# ME433.net
KiCad netlist of a schematic drawn in EAGLE
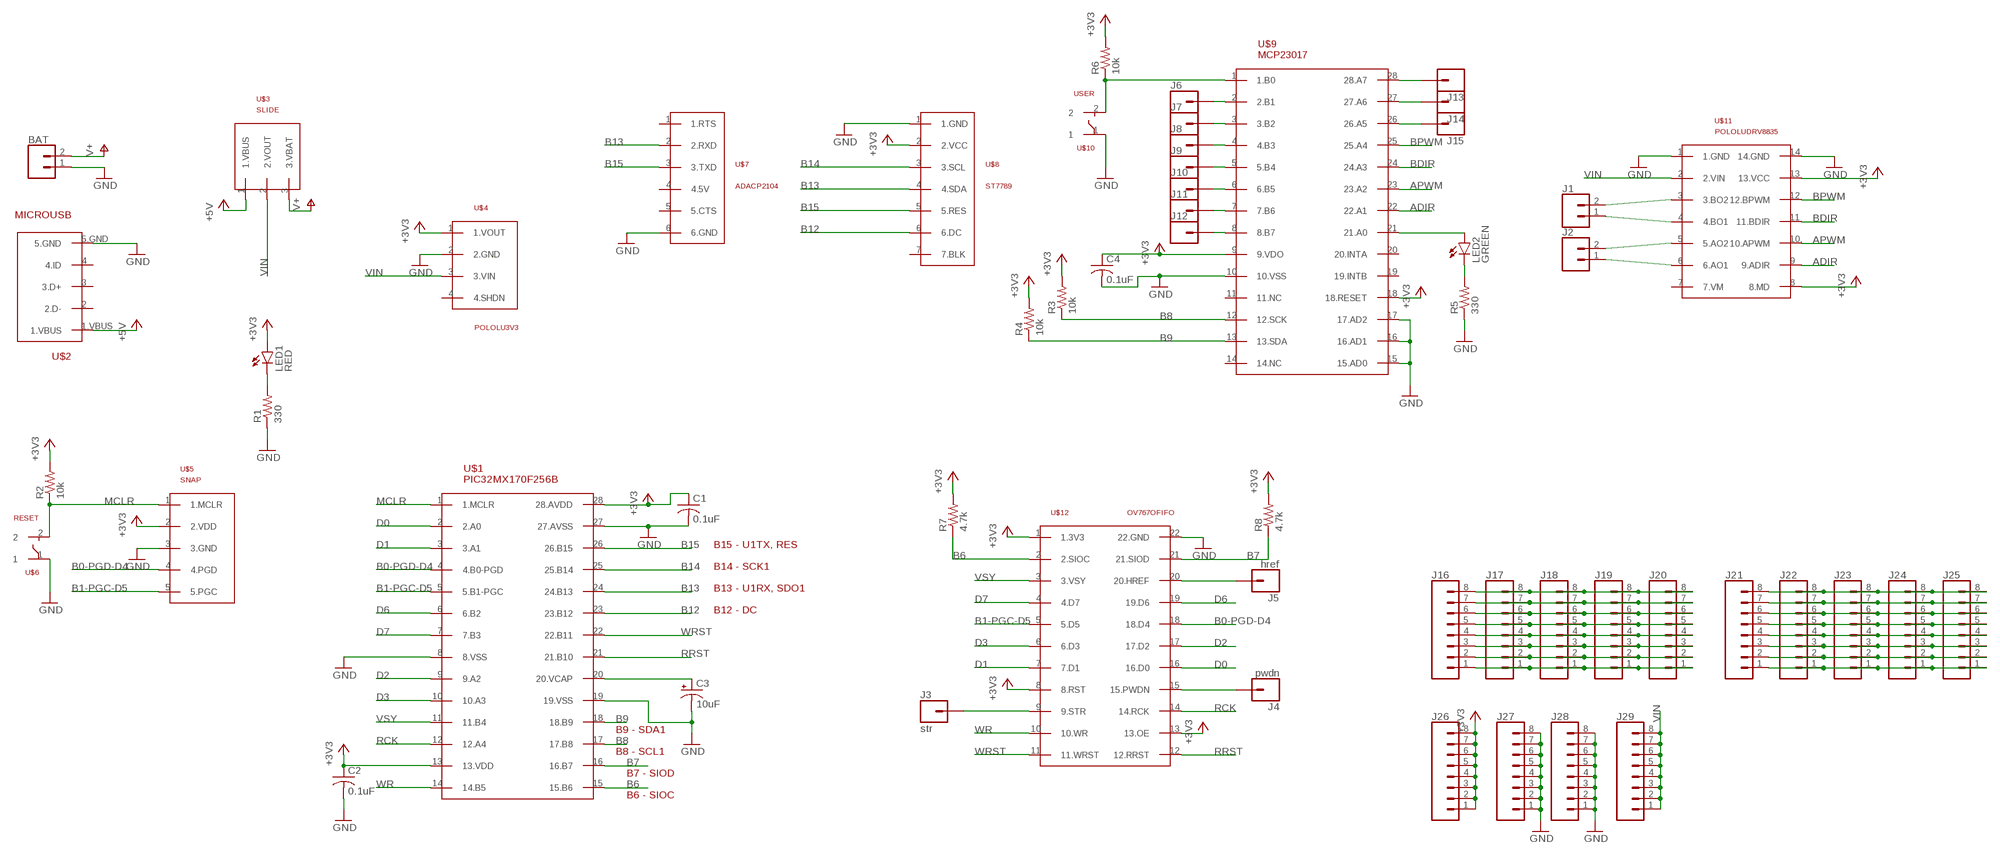
[diagram p0: schematic, sheet 1]

(export (version "E")
  (design (tool "Eeschema 10.0.6"))
  (components
    (comp (ref "BAT")
      (value "CONN_02")
      (footprint "eagle-import:1X02")
      (libsource (lib "eagle-import") (part "CONN_02"))
    )
    (comp (ref "C1")
      (value "0.1uF")
      (footprint "eagle-import:C025-030X050")
      (libsource (lib "eagle-import") (part "C-US025-030X050"))
    )
    (comp (ref "C2")
      (value "0.1uF")
      (footprint "eagle-import:C025-030X050")
      (libsource (lib "eagle-import") (part "C-US025-030X050"))
    )
    (comp (ref "C3")
      (value "10uF")
      (footprint "eagle-import:B45181B")
      (libsource (lib "eagle-import") (part "CPOL-USB45181B"))
    )
    (comp (ref "C4")
      (value "0.1uF")
      (footprint "eagle-import:C025-030X050")
      (libsource (lib "eagle-import") (part "C-US025-030X050"))
    )
    (comp (ref "J1")
      (value "CONN_02")
      (footprint "eagle-import:1X02")
      (libsource (lib "eagle-import") (part "CONN_02"))
    )
    (comp (ref "J2")
      (value "CONN_02")
      (footprint "eagle-import:1X02")
      (libsource (lib "eagle-import") (part "CONN_02"))
    )
    (comp (ref "J3")
      (value "str")
      (footprint "eagle-import:1X01")
      (libsource (lib "eagle-import") (part "CONN_01"))
    )
    (comp (ref "J4")
      (value "pwdn")
      (footprint "eagle-import:1X01")
      (libsource (lib "eagle-import") (part "CONN_01"))
    )
    (comp (ref "J5")
      (value "href")
      (footprint "eagle-import:1X01")
      (libsource (lib "eagle-import") (part "CONN_01"))
    )
    (comp (ref "J6")
      (value "CONN_01")
      (footprint "eagle-import:1X01")
      (libsource (lib "eagle-import") (part "CONN_01"))
    )
    (comp (ref "J7")
      (value "CONN_01")
      (footprint "eagle-import:1X01")
      (libsource (lib "eagle-import") (part "CONN_01"))
    )
    (comp (ref "J8")
      (value "CONN_01")
      (footprint "eagle-import:1X01")
      (libsource (lib "eagle-import") (part "CONN_01"))
    )
    (comp (ref "J9")
      (value "CONN_01")
      (footprint "eagle-import:1X01")
      (libsource (lib "eagle-import") (part "CONN_01"))
    )
    (comp (ref "J10")
      (value "CONN_01")
      (footprint "eagle-import:1X01")
      (libsource (lib "eagle-import") (part "CONN_01"))
    )
    (comp (ref "J11")
      (value "CONN_01")
      (footprint "eagle-import:1X01")
      (libsource (lib "eagle-import") (part "CONN_01"))
    )
    (comp (ref "J12")
      (value "CONN_01")
      (footprint "eagle-import:1X01")
      (libsource (lib "eagle-import") (part "CONN_01"))
    )
    (comp (ref "J13")
      (value "CONN_01")
      (footprint "eagle-import:1X01")
      (libsource (lib "eagle-import") (part "CONN_01"))
    )
    (comp (ref "J14")
      (value "CONN_01")
      (footprint "eagle-import:1X01")
      (libsource (lib "eagle-import") (part "CONN_01"))
    )
    (comp (ref "J15")
      (value "CONN_01")
      (footprint "eagle-import:1X01")
      (libsource (lib "eagle-import") (part "CONN_01"))
    )
    (comp (ref "J16")
      (value "CONN_08\"")
      (footprint "eagle-import:1X08")
      (libsource (lib "eagle-import") (part "CONN_08{dblquote}"))
    )
    (comp (ref "J17")
      (value "CONN_08\"")
      (footprint "eagle-import:1X08")
      (libsource (lib "eagle-import") (part "CONN_08{dblquote}"))
    )
    (comp (ref "J18")
      (value "CONN_08\"")
      (footprint "eagle-import:1X08")
      (libsource (lib "eagle-import") (part "CONN_08{dblquote}"))
    )
    (comp (ref "J19")
      (value "CONN_08\"")
      (footprint "eagle-import:1X08")
      (libsource (lib "eagle-import") (part "CONN_08{dblquote}"))
    )
    (comp (ref "J20")
      (value "CONN_08\"")
      (footprint "eagle-import:1X08")
      (libsource (lib "eagle-import") (part "CONN_08{dblquote}"))
    )
    (comp (ref "J21")
      (value "CONN_08\"")
      (footprint "eagle-import:1X08")
      (libsource (lib "eagle-import") (part "CONN_08{dblquote}"))
    )
    (comp (ref "J22")
      (value "CONN_08\"")
      (footprint "eagle-import:1X08")
      (libsource (lib "eagle-import") (part "CONN_08{dblquote}"))
    )
    (comp (ref "J23")
      (value "CONN_08\"")
      (footprint "eagle-import:1X08")
      (libsource (lib "eagle-import") (part "CONN_08{dblquote}"))
    )
    (comp (ref "J24")
      (value "CONN_08\"")
      (footprint "eagle-import:1X08")
      (libsource (lib "eagle-import") (part "CONN_08{dblquote}"))
    )
    (comp (ref "J25")
      (value "CONN_08\"")
      (footprint "eagle-import:1X08")
      (libsource (lib "eagle-import") (part "CONN_08{dblquote}"))
    )
    (comp (ref "J26")
      (value "CONN_08\"")
      (footprint "eagle-import:1X08")
      (libsource (lib "eagle-import") (part "CONN_08{dblquote}"))
    )
    (comp (ref "J27")
      (value "CONN_08\"")
      (footprint "eagle-import:1X08")
      (libsource (lib "eagle-import") (part "CONN_08{dblquote}"))
    )
    (comp (ref "J28")
      (value "CONN_08\"")
      (footprint "eagle-import:1X08")
      (libsource (lib "eagle-import") (part "CONN_08{dblquote}"))
    )
    (comp (ref "J29")
      (value "CONN_08\"")
      (footprint "eagle-import:1X08")
      (libsource (lib "eagle-import") (part "CONN_08{dblquote}"))
    )
    (comp (ref "LED1")
      (value "RED")
      (footprint "eagle-import:LED3MM")
      (libsource (lib "eagle-import") (part "LED3MM"))
    )
    (comp (ref "LED2")
      (value "GREEN")
      (footprint "eagle-import:LED3MM")
      (libsource (lib "eagle-import") (part "LED3MM"))
    )
    (comp (ref "R1")
      (value "330")
      (footprint "eagle-import:0207_10")
      (libsource (lib "eagle-import") (part "R-US_0207/10"))
    )
    (comp (ref "R2")
      (value "10k")
      (footprint "eagle-import:0207_10")
      (libsource (lib "eagle-import") (part "R-US_0207/10"))
    )
    (comp (ref "R3")
      (value "10k")
      (footprint "eagle-import:0207_10")
      (libsource (lib "eagle-import") (part "R-US_0207/10"))
    )
    (comp (ref "R4")
      (value "10k")
      (footprint "eagle-import:0207_10")
      (libsource (lib "eagle-import") (part "R-US_0207/10"))
    )
    (comp (ref "R5")
      (value "330")
      (footprint "eagle-import:0207_10")
      (libsource (lib "eagle-import") (part "R-US_0207/10"))
    )
    (comp (ref "R6")
      (value "10k")
      (footprint "eagle-import:0207_10")
      (libsource (lib "eagle-import") (part "R-US_0207/10"))
    )
    (comp (ref "R7")
      (value "4.7k")
      (footprint "eagle-import:0207_10")
      (libsource (lib "eagle-import") (part "R-US_0207/10"))
    )
    (comp (ref "R8")
      (value "4.7k")
      (footprint "eagle-import:0207_10")
      (libsource (lib "eagle-import") (part "R-US_0207/10"))
    )
    (comp (ref "U$1")
      (value "PIC32MX170F256B")
      (footprint "eagle-import:DIL28-3")
      (libsource (lib "eagle-import") (part "PIC32MX170F256B"))
    )
    (comp (ref "U$2")
      (value "MICROUSB")
      (footprint "eagle-import:MICROUSB")
      (libsource (lib "eagle-import") (part "MICROUSB"))
    )
    (comp (ref "U$3")
      (value "SLIDE")
      (footprint "eagle-import:SLIDE")
      (libsource (lib "eagle-import") (part "SLIDE"))
    )
    (comp (ref "U$4")
      (value "POLOLU3V3")
      (footprint "eagle-import:POLOLU3V3")
      (libsource (lib "eagle-import") (part "POLOLU3V3"))
    )
    (comp (ref "U$5")
      (value "SNAP")
      (footprint "eagle-import:SNAP")
      (libsource (lib "eagle-import") (part "SNAP"))
    )
    (comp (ref "U$6")
      (value "RESET")
      (footprint "eagle-import:PUSH")
      (libsource (lib "eagle-import") (part "PUSH"))
    )
    (comp (ref "U$7")
      (value "ADACP2104")
      (footprint "eagle-import:ADACP2104")
      (libsource (lib "eagle-import") (part "ADACP2104"))
    )
    (comp (ref "U$8")
      (value "ST7789")
      (footprint "eagle-import:ST7789")
      (libsource (lib "eagle-import") (part "ST7789"))
    )
    (comp (ref "U$9")
      (value "MCP23017")
      (footprint "eagle-import:MCP23017")
      (libsource (lib "eagle-import") (part "MCP23017"))
    )
    (comp (ref "U$10")
      (value "USER")
      (footprint "eagle-import:PUSH")
      (libsource (lib "eagle-import") (part "PUSH"))
    )
    (comp (ref "U$11")
      (value "POLOLUDRV8835")
      (footprint "eagle-import:POLOLUDRV8835")
      (libsource (lib "eagle-import") (part "POLOLUDRV8835"))
    )
    (comp (ref "U$12")
      (value "OV767OFIFO")
      (footprint "eagle-import:OV767OFIFO")
      (libsource (lib "eagle-import") (part "OV767OFIFO"))
    )
  )
  (nets
    (net (code "1") (name "+3V3") (class "Default")
      (node (ref "C1") (pin "1") (pinfunction "1_1") (pintype "passive"))
      (node (ref "C2") (pin "1") (pinfunction "1_1") (pintype "passive"))
      (node (ref "C4") (pin "1") (pinfunction "1_1") (pintype "passive"))
      (node (ref "J26") (pin "1") (pinfunction "1_1") (pintype "passive"))
      (node (ref "J26") (pin "2") (pinfunction "2_2") (pintype "passive"))
      (node (ref "J26") (pin "3") (pinfunction "3_3") (pintype "passive"))
      (node (ref "J26") (pin "4") (pinfunction "4_4") (pintype "passive"))
      (node (ref "J26") (pin "5") (pinfunction "5_5") (pintype "passive"))
      (node (ref "J26") (pin "6") (pinfunction "6_6") (pintype "passive"))
      (node (ref "J26") (pin "7") (pinfunction "7_7") (pintype "passive"))
      (node (ref "J26") (pin "8") (pinfunction "8_8") (pintype "passive"))
      (node (ref "LED1") (pin "A") (pinfunction "A_A") (pintype "passive"))
      (node (ref "R2") (pin "2") (pinfunction "2_2") (pintype "passive"))
      (node (ref "R3") (pin "2") (pinfunction "2_2") (pintype "passive"))
      (node (ref "R4") (pin "2") (pinfunction "2_2") (pintype "passive"))
      (node (ref "R6") (pin "2") (pinfunction "2_2") (pintype "passive"))
      (node (ref "R7") (pin "2") (pinfunction "2_2") (pintype "passive"))
      (node (ref "R8") (pin "2") (pinfunction "2_2") (pintype "passive"))
      (node (ref "U$1") (pin "13") (pinfunction "13.VDD_13") (pintype "bidirectional"))
      (node (ref "U$1") (pin "28") (pinfunction "28.AVDD_28") (pintype "bidirectional"))
      (node (ref "U$11") (pin "13") (pinfunction "13.VCC_13") (pintype "bidirectional"))
      (node (ref "U$11") (pin "8") (pinfunction "8.MD_8") (pintype "bidirectional"))
      (node (ref "U$12") (pin "1") (pinfunction "1.3V3_1") (pintype "bidirectional"))
      (node (ref "U$12") (pin "13") (pinfunction "13.OE_13") (pintype "bidirectional"))
      (node (ref "U$12") (pin "8") (pinfunction "8.RST_8") (pintype "bidirectional"))
      (node (ref "U$4") (pin "1") (pinfunction "1.VOUT_1") (pintype "bidirectional"))
      (node (ref "U$5") (pin "2") (pinfunction "2.VDD_2") (pintype "bidirectional"))
      (node (ref "U$8") (pin "2") (pinfunction "2.VCC_2") (pintype "bidirectional"))
      (node (ref "U$9") (pin "18") (pinfunction "18.RESET_18") (pintype "bidirectional"))
      (node (ref "U$9") (pin "9") (pinfunction "9.VDO_9") (pintype "bidirectional"))
    )
    (net (code "2") (name "+5V") (class "Default")
      (node (ref "U$2") (pin "1.VBUS") (pinfunction "1.VBUS_1.VBUS") (pintype "bidirectional"))
      (node (ref "U$3") (pin "1") (pinfunction "1.VBUS_1") (pintype "bidirectional"))
    )
    (net (code "3") (name "/ADIR") (class "Default")
      (node (ref "U$11") (pin "9") (pinfunction "9.ADIR_9") (pintype "bidirectional"))
      (node (ref "U$9") (pin "22") (pinfunction "22.A1_22") (pintype "bidirectional"))
    )
    (net (code "4") (name "/APWM") (class "Default")
      (node (ref "U$11") (pin "10.") (pinfunction "10.APWM_10.") (pintype "bidirectional"))
      (node (ref "U$9") (pin "23") (pinfunction "23.A2_23") (pintype "bidirectional"))
    )
    (net (code "5") (name "/B0-PGD-D4") (class "Default")
      (node (ref "U$1") (pin "4") (pinfunction "4.B0-PGD_4") (pintype "bidirectional"))
      (node (ref "U$12") (pin "18") (pinfunction "18.D4_18") (pintype "bidirectional"))
      (node (ref "U$5") (pin "4") (pinfunction "4.PGD_4") (pintype "bidirectional"))
    )
    (net (code "6") (name "/B1-PGC-D5") (class "Default")
      (node (ref "U$1") (pin "5") (pinfunction "5.B1-PGC_5") (pintype "bidirectional"))
      (node (ref "U$12") (pin "5") (pinfunction "5.D5_5") (pintype "bidirectional"))
      (node (ref "U$5") (pin "5") (pinfunction "5.PGC_5") (pintype "bidirectional"))
    )
    (net (code "7") (name "/B6") (class "Default")
      (node (ref "R7") (pin "1") (pinfunction "1_1") (pintype "passive"))
      (node (ref "U$1") (pin "15") (pinfunction "15.B6_15") (pintype "bidirectional"))
      (node (ref "U$12") (pin "2") (pinfunction "2.SIOC_2") (pintype "bidirectional"))
    )
    (net (code "8") (name "/B7") (class "Default")
      (node (ref "R8") (pin "1") (pinfunction "1_1") (pintype "passive"))
      (node (ref "U$1") (pin "16") (pinfunction "16.B7_16") (pintype "bidirectional"))
      (node (ref "U$12") (pin "21") (pinfunction "21.SIOD_21") (pintype "bidirectional"))
    )
    (net (code "9") (name "/B8") (class "Default")
      (node (ref "R3") (pin "1") (pinfunction "1_1") (pintype "passive"))
      (node (ref "U$1") (pin "17") (pinfunction "17.B8_17") (pintype "bidirectional"))
      (node (ref "U$9") (pin "12") (pinfunction "12.SCK_12") (pintype "bidirectional"))
    )
    (net (code "10") (name "/B9") (class "Default")
      (node (ref "R4") (pin "1") (pinfunction "1_1") (pintype "passive"))
      (node (ref "U$1") (pin "18") (pinfunction "18.B9_18") (pintype "bidirectional"))
      (node (ref "U$9") (pin "13") (pinfunction "13.SDA_13") (pintype "bidirectional"))
    )
    (net (code "11") (name "/B12") (class "Default")
      (node (ref "U$1") (pin "23") (pinfunction "23.B12_23") (pintype "bidirectional"))
      (node (ref "U$8") (pin "6") (pinfunction "6.DC_6") (pintype "bidirectional"))
    )
    (net (code "12") (name "/B13") (class "Default")
      (node (ref "U$1") (pin "24") (pinfunction "24.B13_24") (pintype "bidirectional"))
      (node (ref "U$7") (pin "2") (pinfunction "2.RXD_2") (pintype "bidirectional"))
      (node (ref "U$8") (pin "4") (pinfunction "4.SDA_4") (pintype "bidirectional"))
    )
    (net (code "13") (name "/B14") (class "Default")
      (node (ref "U$1") (pin "25") (pinfunction "25.B14_25") (pintype "bidirectional"))
      (node (ref "U$8") (pin "3") (pinfunction "3.SCL_3") (pintype "bidirectional"))
    )
    (net (code "14") (name "/B15") (class "Default")
      (node (ref "U$1") (pin "26") (pinfunction "26.B15_26") (pintype "bidirectional"))
      (node (ref "U$7") (pin "3") (pinfunction "3.TXD_3") (pintype "bidirectional"))
      (node (ref "U$8") (pin "5") (pinfunction "5.RES_5") (pintype "bidirectional"))
    )
    (net (code "15") (name "/BDIR") (class "Default")
      (node (ref "U$11") (pin "11") (pinfunction "11.BDIR_11") (pintype "bidirectional"))
      (node (ref "U$9") (pin "24") (pinfunction "24.A3_24") (pintype "bidirectional"))
    )
    (net (code "16") (name "/BPWM") (class "Default")
      (node (ref "U$11") (pin "12") (pinfunction "12.BPWM_12") (pintype "bidirectional"))
      (node (ref "U$9") (pin "25") (pinfunction "25.A4_25") (pintype "bidirectional"))
    )
    (net (code "17") (name "/D0") (class "Default")
      (node (ref "U$1") (pin "2") (pinfunction "2.A0_2") (pintype "bidirectional"))
      (node (ref "U$12") (pin "16") (pinfunction "16.D0_16") (pintype "bidirectional"))
    )
    (net (code "18") (name "/D1") (class "Default")
      (node (ref "U$1") (pin "3") (pinfunction "3.A1_3") (pintype "bidirectional"))
      (node (ref "U$12") (pin "7") (pinfunction "7.D1_7") (pintype "bidirectional"))
    )
    (net (code "19") (name "/D2") (class "Default")
      (node (ref "U$1") (pin "9") (pinfunction "9.A2_9") (pintype "bidirectional"))
      (node (ref "U$12") (pin "17") (pinfunction "17.D2_17") (pintype "bidirectional"))
    )
    (net (code "20") (name "/D3") (class "Default")
      (node (ref "U$1") (pin "10") (pinfunction "10.A3_10") (pintype "bidirectional"))
      (node (ref "U$12") (pin "6") (pinfunction "6.D3_6") (pintype "bidirectional"))
    )
    (net (code "21") (name "/D6") (class "Default")
      (node (ref "U$1") (pin "6") (pinfunction "6.B2_6") (pintype "bidirectional"))
      (node (ref "U$12") (pin "19") (pinfunction "19.D6_19") (pintype "bidirectional"))
    )
    (net (code "22") (name "/D7") (class "Default")
      (node (ref "U$1") (pin "7") (pinfunction "7.B3_7") (pintype "bidirectional"))
      (node (ref "U$12") (pin "4") (pinfunction "4.D7_4") (pintype "bidirectional"))
    )
    (net (code "23") (name "/MCLR") (class "Default")
      (node (ref "R2") (pin "1") (pinfunction "1_1") (pintype "passive"))
      (node (ref "U$1") (pin "1") (pinfunction "1.MCLR_1") (pintype "bidirectional"))
      (node (ref "U$5") (pin "1") (pinfunction "1.MCLR_1") (pintype "bidirectional"))
      (node (ref "U$6") (pin "2") (pinfunction "2_2") (pintype "bidirectional"))
    )
    (net (code "24") (name "/RCK") (class "Default")
      (node (ref "U$1") (pin "12") (pinfunction "12.A4_12") (pintype "bidirectional"))
      (node (ref "U$12") (pin "14") (pinfunction "14.RCK_14") (pintype "bidirectional"))
    )
    (net (code "25") (name "/RRST") (class "Default")
      (node (ref "U$1") (pin "21") (pinfunction "21.B10_21") (pintype "bidirectional"))
      (node (ref "U$12") (pin "12") (pinfunction "12.RRST_12") (pintype "bidirectional"))
    )
    (net (code "26") (name "/VIN") (class "Default")
      (node (ref "J29") (pin "1") (pinfunction "1_1") (pintype "passive"))
      (node (ref "J29") (pin "2") (pinfunction "2_2") (pintype "passive"))
      (node (ref "J29") (pin "3") (pinfunction "3_3") (pintype "passive"))
      (node (ref "J29") (pin "4") (pinfunction "4_4") (pintype "passive"))
      (node (ref "J29") (pin "5") (pinfunction "5_5") (pintype "passive"))
      (node (ref "J29") (pin "6") (pinfunction "6_6") (pintype "passive"))
      (node (ref "J29") (pin "7") (pinfunction "7_7") (pintype "passive"))
      (node (ref "J29") (pin "8") (pinfunction "8_8") (pintype "passive"))
      (node (ref "U$11") (pin "2") (pinfunction "2.VIN_2") (pintype "bidirectional"))
      (node (ref "U$3") (pin "2") (pinfunction "2.VOUT_2") (pintype "bidirectional"))
      (node (ref "U$4") (pin "3") (pinfunction "3.VIN_3") (pintype "bidirectional"))
    )
    (net (code "27") (name "/VSY") (class "Default")
      (node (ref "U$1") (pin "11") (pinfunction "11.B4_11") (pintype "bidirectional"))
      (node (ref "U$12") (pin "3") (pinfunction "3.VSY_3") (pintype "bidirectional"))
    )
    (net (code "28") (name "/WR") (class "Default")
      (node (ref "U$1") (pin "14") (pinfunction "14.B5_14") (pintype "bidirectional"))
      (node (ref "U$12") (pin "10") (pinfunction "10.WR_10") (pintype "bidirectional"))
    )
    (net (code "29") (name "/WRST") (class "Default")
      (node (ref "U$1") (pin "22") (pinfunction "22.B11_22") (pintype "bidirectional"))
      (node (ref "U$12") (pin "11") (pinfunction "11.WRST_11") (pintype "bidirectional"))
    )
    (net (code "30") (name "GND") (class "Default")
      (node (ref "BAT") (pin "1") (pinfunction "1_1") (pintype "passive"))
      (node (ref "C1") (pin "2") (pinfunction "2_2") (pintype "passive"))
      (node (ref "C2") (pin "2") (pinfunction "2_2") (pintype "passive"))
      (node (ref "C3") (pin "-") (pinfunction "-_-") (pintype "passive"))
      (node (ref "C4") (pin "2") (pinfunction "2_2") (pintype "passive"))
      (node (ref "J27") (pin "1") (pinfunction "1_1") (pintype "passive"))
      (node (ref "J27") (pin "2") (pinfunction "2_2") (pintype "passive"))
      (node (ref "J27") (pin "3") (pinfunction "3_3") (pintype "passive"))
      (node (ref "J27") (pin "4") (pinfunction "4_4") (pintype "passive"))
      (node (ref "J27") (pin "5") (pinfunction "5_5") (pintype "passive"))
      (node (ref "J27") (pin "6") (pinfunction "6_6") (pintype "passive"))
      (node (ref "J27") (pin "7") (pinfunction "7_7") (pintype "passive"))
      (node (ref "J27") (pin "8") (pinfunction "8_8") (pintype "passive"))
      (node (ref "J28") (pin "1") (pinfunction "1_1") (pintype "passive"))
      (node (ref "J28") (pin "2") (pinfunction "2_2") (pintype "passive"))
      (node (ref "J28") (pin "3") (pinfunction "3_3") (pintype "passive"))
      (node (ref "J28") (pin "4") (pinfunction "4_4") (pintype "passive"))
      (node (ref "J28") (pin "5") (pinfunction "5_5") (pintype "passive"))
      (node (ref "J28") (pin "6") (pinfunction "6_6") (pintype "passive"))
      (node (ref "J28") (pin "7") (pinfunction "7_7") (pintype "passive"))
      (node (ref "J28") (pin "8") (pinfunction "8_8") (pintype "passive"))
      (node (ref "R1") (pin "1") (pinfunction "1_1") (pintype "passive"))
      (node (ref "R5") (pin "1") (pinfunction "1_1") (pintype "passive"))
      (node (ref "U$1") (pin "19") (pinfunction "19.VSS_19") (pintype "bidirectional"))
      (node (ref "U$1") (pin "27") (pinfunction "27.AVSS_27") (pintype "bidirectional"))
      (node (ref "U$1") (pin "8") (pinfunction "8.VSS_8") (pintype "bidirectional"))
      (node (ref "U$10") (pin "1") (pinfunction "1_1") (pintype "bidirectional"))
      (node (ref "U$11") (pin "1") (pinfunction "1.GND_1") (pintype "bidirectional"))
      (node (ref "U$11") (pin "14") (pinfunction "14.GND_14") (pintype "bidirectional"))
      (node (ref "U$12") (pin "22") (pinfunction "22.GND_22") (pintype "bidirectional"))
      (node (ref "U$2") (pin "5.GND") (pinfunction "5.GND_5.GND") (pintype "bidirectional"))
      (node (ref "U$4") (pin "2") (pinfunction "2.GND_2") (pintype "bidirectional"))
      (node (ref "U$5") (pin "3") (pinfunction "3.GND_3") (pintype "bidirectional"))
      (node (ref "U$6") (pin "1") (pinfunction "1_1") (pintype "bidirectional"))
      (node (ref "U$7") (pin "6") (pinfunction "6.GND_6") (pintype "bidirectional"))
      (node (ref "U$8") (pin "1") (pinfunction "1.GND_1") (pintype "bidirectional"))
      (node (ref "U$9") (pin "10") (pinfunction "10.VSS_10") (pintype "bidirectional"))
      (node (ref "U$9") (pin "15") (pinfunction "15.AD0_15") (pintype "bidirectional"))
      (node (ref "U$9") (pin "16") (pinfunction "16.AD1_16") (pintype "bidirectional"))
      (node (ref "U$9") (pin "17") (pinfunction "17.AD2_17") (pintype "bidirectional"))
    )
    (net (code "31") (name "Net-(J16-Pad1)") (class "Default")
      (node (ref "J16") (pin "1") (pinfunction "1_1") (pintype "passive"))
      (node (ref "J17") (pin "1") (pinfunction "1_1") (pintype "passive"))
      (node (ref "J18") (pin "1") (pinfunction "1_1") (pintype "passive"))
      (node (ref "J19") (pin "1") (pinfunction "1_1") (pintype "passive"))
      (node (ref "J20") (pin "1") (pinfunction "1_1") (pintype "passive"))
    )
    (net (code "32") (name "Net-(J16-Pad2)") (class "Default")
      (node (ref "J16") (pin "2") (pinfunction "2_2") (pintype "passive"))
      (node (ref "J17") (pin "2") (pinfunction "2_2") (pintype "passive"))
      (node (ref "J18") (pin "2") (pinfunction "2_2") (pintype "passive"))
      (node (ref "J19") (pin "2") (pinfunction "2_2") (pintype "passive"))
      (node (ref "J20") (pin "2") (pinfunction "2_2") (pintype "passive"))
    )
    (net (code "33") (name "Net-(J16-Pad3)") (class "Default")
      (node (ref "J16") (pin "3") (pinfunction "3_3") (pintype "passive"))
      (node (ref "J17") (pin "3") (pinfunction "3_3") (pintype "passive"))
      (node (ref "J18") (pin "3") (pinfunction "3_3") (pintype "passive"))
      (node (ref "J19") (pin "3") (pinfunction "3_3") (pintype "passive"))
      (node (ref "J20") (pin "3") (pinfunction "3_3") (pintype "passive"))
    )
    (net (code "34") (name "Net-(J16-Pad4)") (class "Default")
      (node (ref "J16") (pin "4") (pinfunction "4_4") (pintype "passive"))
      (node (ref "J17") (pin "4") (pinfunction "4_4") (pintype "passive"))
      (node (ref "J18") (pin "4") (pinfunction "4_4") (pintype "passive"))
      (node (ref "J19") (pin "4") (pinfunction "4_4") (pintype "passive"))
      (node (ref "J20") (pin "4") (pinfunction "4_4") (pintype "passive"))
    )
    (net (code "35") (name "Net-(J16-Pad5)") (class "Default")
      (node (ref "J16") (pin "5") (pinfunction "5_5") (pintype "passive"))
      (node (ref "J17") (pin "5") (pinfunction "5_5") (pintype "passive"))
      (node (ref "J18") (pin "5") (pinfunction "5_5") (pintype "passive"))
      (node (ref "J19") (pin "5") (pinfunction "5_5") (pintype "passive"))
      (node (ref "J20") (pin "5") (pinfunction "5_5") (pintype "passive"))
    )
    (net (code "36") (name "Net-(J16-Pad6)") (class "Default")
      (node (ref "J16") (pin "6") (pinfunction "6_6") (pintype "passive"))
      (node (ref "J17") (pin "6") (pinfunction "6_6") (pintype "passive"))
      (node (ref "J18") (pin "6") (pinfunction "6_6") (pintype "passive"))
      (node (ref "J19") (pin "6") (pinfunction "6_6") (pintype "passive"))
      (node (ref "J20") (pin "6") (pinfunction "6_6") (pintype "passive"))
    )
    (net (code "37") (name "Net-(J16-Pad7)") (class "Default")
      (node (ref "J16") (pin "7") (pinfunction "7_7") (pintype "passive"))
      (node (ref "J17") (pin "7") (pinfunction "7_7") (pintype "passive"))
      (node (ref "J18") (pin "7") (pinfunction "7_7") (pintype "passive"))
      (node (ref "J19") (pin "7") (pinfunction "7_7") (pintype "passive"))
      (node (ref "J20") (pin "7") (pinfunction "7_7") (pintype "passive"))
    )
    (net (code "38") (name "Net-(J16-Pad8)") (class "Default")
      (node (ref "J16") (pin "8") (pinfunction "8_8") (pintype "passive"))
      (node (ref "J17") (pin "8") (pinfunction "8_8") (pintype "passive"))
      (node (ref "J18") (pin "8") (pinfunction "8_8") (pintype "passive"))
      (node (ref "J19") (pin "8") (pinfunction "8_8") (pintype "passive"))
      (node (ref "J20") (pin "8") (pinfunction "8_8") (pintype "passive"))
    )
    (net (code "39") (name "Net-(J21-Pad1)") (class "Default")
      (node (ref "J21") (pin "1") (pinfunction "1_1") (pintype "passive"))
      (node (ref "J22") (pin "1") (pinfunction "1_1") (pintype "passive"))
      (node (ref "J23") (pin "1") (pinfunction "1_1") (pintype "passive"))
      (node (ref "J24") (pin "1") (pinfunction "1_1") (pintype "passive"))
      (node (ref "J25") (pin "1") (pinfunction "1_1") (pintype "passive"))
    )
    (net (code "40") (name "Net-(J21-Pad2)") (class "Default")
      (node (ref "J21") (pin "2") (pinfunction "2_2") (pintype "passive"))
      (node (ref "J22") (pin "2") (pinfunction "2_2") (pintype "passive"))
      (node (ref "J23") (pin "2") (pinfunction "2_2") (pintype "passive"))
      (node (ref "J24") (pin "2") (pinfunction "2_2") (pintype "passive"))
      (node (ref "J25") (pin "2") (pinfunction "2_2") (pintype "passive"))
    )
    (net (code "41") (name "Net-(J21-Pad3)") (class "Default")
      (node (ref "J21") (pin "3") (pinfunction "3_3") (pintype "passive"))
      (node (ref "J22") (pin "3") (pinfunction "3_3") (pintype "passive"))
      (node (ref "J23") (pin "3") (pinfunction "3_3") (pintype "passive"))
      (node (ref "J24") (pin "3") (pinfunction "3_3") (pintype "passive"))
      (node (ref "J25") (pin "3") (pinfunction "3_3") (pintype "passive"))
    )
    (net (code "42") (name "Net-(J21-Pad4)") (class "Default")
      (node (ref "J21") (pin "4") (pinfunction "4_4") (pintype "passive"))
      (node (ref "J22") (pin "4") (pinfunction "4_4") (pintype "passive"))
      (node (ref "J23") (pin "4") (pinfunction "4_4") (pintype "passive"))
      (node (ref "J24") (pin "4") (pinfunction "4_4") (pintype "passive"))
      (node (ref "J25") (pin "4") (pinfunction "4_4") (pintype "passive"))
    )
    (net (code "43") (name "Net-(J21-Pad5)") (class "Default")
      (node (ref "J21") (pin "5") (pinfunction "5_5") (pintype "passive"))
      (node (ref "J22") (pin "5") (pinfunction "5_5") (pintype "passive"))
      (node (ref "J23") (pin "5") (pinfunction "5_5") (pintype "passive"))
      (node (ref "J24") (pin "5") (pinfunction "5_5") (pintype "passive"))
      (node (ref "J25") (pin "5") (pinfunction "5_5") (pintype "passive"))
    )
    (net (code "44") (name "Net-(J21-Pad6)") (class "Default")
      (node (ref "J21") (pin "6") (pinfunction "6_6") (pintype "passive"))
      (node (ref "J22") (pin "6") (pinfunction "6_6") (pintype "passive"))
      (node (ref "J23") (pin "6") (pinfunction "6_6") (pintype "passive"))
      (node (ref "J24") (pin "6") (pinfunction "6_6") (pintype "passive"))
      (node (ref "J25") (pin "6") (pinfunction "6_6") (pintype "passive"))
    )
    (net (code "45") (name "Net-(J21-Pad7)") (class "Default")
      (node (ref "J21") (pin "7") (pinfunction "7_7") (pintype "passive"))
      (node (ref "J22") (pin "7") (pinfunction "7_7") (pintype "passive"))
      (node (ref "J23") (pin "7") (pinfunction "7_7") (pintype "passive"))
      (node (ref "J24") (pin "7") (pinfunction "7_7") (pintype "passive"))
      (node (ref "J25") (pin "7") (pinfunction "7_7") (pintype "passive"))
    )
    (net (code "46") (name "Net-(J21-Pad8)") (class "Default")
      (node (ref "J21") (pin "8") (pinfunction "8_8") (pintype "passive"))
      (node (ref "J22") (pin "8") (pinfunction "8_8") (pintype "passive"))
      (node (ref "J23") (pin "8") (pinfunction "8_8") (pintype "passive"))
      (node (ref "J24") (pin "8") (pinfunction "8_8") (pintype "passive"))
      (node (ref "J25") (pin "8") (pinfunction "8_8") (pintype "passive"))
    )
    (net (code "47") (name "Net-(LED1-C)") (class "Default")
      (node (ref "LED1") (pin "K") (pinfunction "C_K") (pintype "passive"))
      (node (ref "R1") (pin "2") (pinfunction "2_2") (pintype "passive"))
    )
    (net (code "48") (name "Net-(LED2-C)") (class "Default")
      (node (ref "LED2") (pin "K") (pinfunction "C_K") (pintype "passive"))
      (node (ref "R5") (pin "2") (pinfunction "2_2") (pintype "passive"))
    )
    (net (code "49") (name "Net-(U$1-20.VCAP)") (class "Default")
      (node (ref "C3") (pin "+") (pinfunction "+_+") (pintype "passive"))
      (node (ref "U$1") (pin "20") (pinfunction "20.VCAP_20") (pintype "bidirectional"))
    )
    (net (code "50") (name "Net-(U$9-1.B0)") (class "Default")
      (node (ref "R6") (pin "1") (pinfunction "1_1") (pintype "passive"))
      (node (ref "U$10") (pin "2") (pinfunction "2_2") (pintype "bidirectional"))
      (node (ref "U$9") (pin "1") (pinfunction "1.B0_1") (pintype "bidirectional"))
    )
    (net (code "51") (name "Net-(U$9-2.B1)") (class "Default")
      (node (ref "J6") (pin "1") (pinfunction "1_1") (pintype "passive"))
      (node (ref "U$9") (pin "2") (pinfunction "2.B1_2") (pintype "bidirectional"))
    )
    (net (code "52") (name "Net-(U$9-3.B2)") (class "Default")
      (node (ref "J7") (pin "1") (pinfunction "1_1") (pintype "passive"))
      (node (ref "U$9") (pin "3") (pinfunction "3.B2_3") (pintype "bidirectional"))
    )
    (net (code "53") (name "Net-(U$9-4.B3)") (class "Default")
      (node (ref "J8") (pin "1") (pinfunction "1_1") (pintype "passive"))
      (node (ref "U$9") (pin "4") (pinfunction "4.B3_4") (pintype "bidirectional"))
    )
    (net (code "54") (name "Net-(U$9-5.B4)") (class "Default")
      (node (ref "J9") (pin "1") (pinfunction "1_1") (pintype "passive"))
      (node (ref "U$9") (pin "5") (pinfunction "5.B4_5") (pintype "bidirectional"))
    )
    (net (code "55") (name "Net-(U$9-6.B5)") (class "Default")
      (node (ref "J10") (pin "1") (pinfunction "1_1") (pintype "passive"))
      (node (ref "U$9") (pin "6") (pinfunction "6.B5_6") (pintype "bidirectional"))
    )
    (net (code "56") (name "Net-(U$9-7.B6)") (class "Default")
      (node (ref "J11") (pin "1") (pinfunction "1_1") (pintype "passive"))
      (node (ref "U$9") (pin "7") (pinfunction "7.B6_7") (pintype "bidirectional"))
    )
    (net (code "57") (name "Net-(U$9-8.B7)") (class "Default")
      (node (ref "J12") (pin "1") (pinfunction "1_1") (pintype "passive"))
      (node (ref "U$9") (pin "8") (pinfunction "8.B7_8") (pintype "bidirectional"))
    )
    (net (code "58") (name "Net-(U$9-21.A0)") (class "Default")
      (node (ref "LED2") (pin "A") (pinfunction "A_A") (pintype "passive"))
      (node (ref "U$9") (pin "21") (pinfunction "21.A0_21") (pintype "bidirectional"))
    )
    (net (code "59") (name "Net-(U$9-26.A5)") (class "Default")
      (node (ref "J15") (pin "1") (pinfunction "1_1") (pintype "passive"))
      (node (ref "U$9") (pin "26") (pinfunction "26.A5_26") (pintype "bidirectional"))
    )
    (net (code "60") (name "Net-(U$9-27.A6)") (class "Default")
      (node (ref "J14") (pin "1") (pinfunction "1_1") (pintype "passive"))
      (node (ref "U$9") (pin "27") (pinfunction "27.A6_27") (pintype "bidirectional"))
    )
    (net (code "61") (name "Net-(U$9-28.A7)") (class "Default")
      (node (ref "J13") (pin "1") (pinfunction "1_1") (pintype "passive"))
      (node (ref "U$9") (pin "28") (pinfunction "28.A7_28") (pintype "bidirectional"))
    )
    (net (code "62") (name "Net-(U$11-3.BO2)") (class "Default")
      (node (ref "J1") (pin "2") (pinfunction "2_2") (pintype "passive"))
      (node (ref "U$11") (pin "3") (pinfunction "3.BO2_3") (pintype "bidirectional"))
    )
    (net (code "63") (name "Net-(U$11-4.BO1)") (class "Default")
      (node (ref "J1") (pin "1") (pinfunction "1_1") (pintype "passive"))
      (node (ref "U$11") (pin "4") (pinfunction "4.BO1_4") (pintype "bidirectional"))
    )
    (net (code "64") (name "Net-(U$11-5.AO2)") (class "Default")
      (node (ref "J2") (pin "2") (pinfunction "2_2") (pintype "passive"))
      (node (ref "U$11") (pin "5") (pinfunction "5.AO2_5") (pintype "bidirectional"))
    )
    (net (code "65") (name "Net-(U$11-6.AO1)") (class "Default")
      (node (ref "J2") (pin "1") (pinfunction "1_1") (pintype "passive"))
      (node (ref "U$11") (pin "6") (pinfunction "6.AO1_6") (pintype "bidirectional"))
    )
    (net (code "66") (name "Net-(U$12-9.STR)") (class "Default")
      (node (ref "J3") (pin "1") (pinfunction "1_1") (pintype "passive"))
      (node (ref "U$12") (pin "9") (pinfunction "9.STR_9") (pintype "bidirectional"))
    )
    (net (code "67") (name "Net-(U$12-15.PWDN)") (class "Default")
      (node (ref "J4") (pin "1") (pinfunction "1_1") (pintype "passive"))
      (node (ref "U$12") (pin "15") (pinfunction "15.PWDN_15") (pintype "bidirectional"))
    )
    (net (code "68") (name "Net-(U$12-20.HREF)") (class "Default")
      (node (ref "J5") (pin "1") (pinfunction "1_1") (pintype "passive"))
      (node (ref "U$12") (pin "20") (pinfunction "20.HREF_20") (pintype "bidirectional"))
    )
    (net (code "69") (name "V+") (class "Default")
      (node (ref "BAT") (pin "2") (pinfunction "2_2") (pintype "passive"))
      (node (ref "U$3") (pin "3") (pinfunction "3.VBAT_3") (pintype "bidirectional"))
    )
    (net (code "70") (name "unconnected-(U$2-2.D--Pad2)") (class "Default")
      (node (ref "U$2") (pin "2") (pinfunction "2.D-_2") (pintype "bidirectional"))
    )
    (net (code "71") (name "unconnected-(U$2-3.D+-Pad3)") (class "Default")
      (node (ref "U$2") (pin "3") (pinfunction "3.D+_3") (pintype "bidirectional"))
    )
    (net (code "72") (name "unconnected-(U$2-4.ID-Pad4)") (class "Default")
      (node (ref "U$2") (pin "4") (pinfunction "4.ID_4") (pintype "bidirectional"))
    )
    (net (code "73") (name "unconnected-(U$4-4.SHDN-Pad4)") (class "Default")
      (node (ref "U$4") (pin "4") (pinfunction "4.SHDN_4") (pintype "bidirectional"))
    )
    (net (code "74") (name "unconnected-(U$7-1.RTS-Pad1)") (class "Default")
      (node (ref "U$7") (pin "1") (pinfunction "1.RTS_1") (pintype "bidirectional"))
    )
    (net (code "75") (name "unconnected-(U$7-4.5V-Pad4)") (class "Default")
      (node (ref "U$7") (pin "4") (pinfunction "4.5V_4") (pintype "bidirectional"))
    )
    (net (code "76") (name "unconnected-(U$7-5.CTS-Pad5)") (class "Default")
      (node (ref "U$7") (pin "5") (pinfunction "5.CTS_5") (pintype "bidirectional"))
    )
    (net (code "77") (name "unconnected-(U$8-7.BLK-Pad7)") (class "Default")
      (node (ref "U$8") (pin "7") (pinfunction "7.BLK_7") (pintype "bidirectional"))
    )
    (net (code "78") (name "unconnected-(U$9-11.NC-Pad11)") (class "Default")
      (node (ref "U$9") (pin "11") (pinfunction "11.NC_11") (pintype "bidirectional"))
    )
    (net (code "79") (name "unconnected-(U$9-14.NC-Pad14)") (class "Default")
      (node (ref "U$9") (pin "14") (pinfunction "14.NC_14") (pintype "bidirectional"))
    )
    (net (code "80") (name "unconnected-(U$9-19.INTB-Pad19)") (class "Default")
      (node (ref "U$9") (pin "19") (pinfunction "19.INTB_19") (pintype "bidirectional"))
    )
    (net (code "81") (name "unconnected-(U$9-20.INTA-Pad20)") (class "Default")
      (node (ref "U$9") (pin "20") (pinfunction "20.INTA_20") (pintype "bidirectional"))
    )
    (net (code "82") (name "unconnected-(U$11-7.VM-Pad7)") (class "Default")
      (node (ref "U$11") (pin "7") (pinfunction "7.VM_7") (pintype "bidirectional"))
    )
  )
)
